# usbjtag.net
KiCad netlist of a schematic drawn in EAGLE
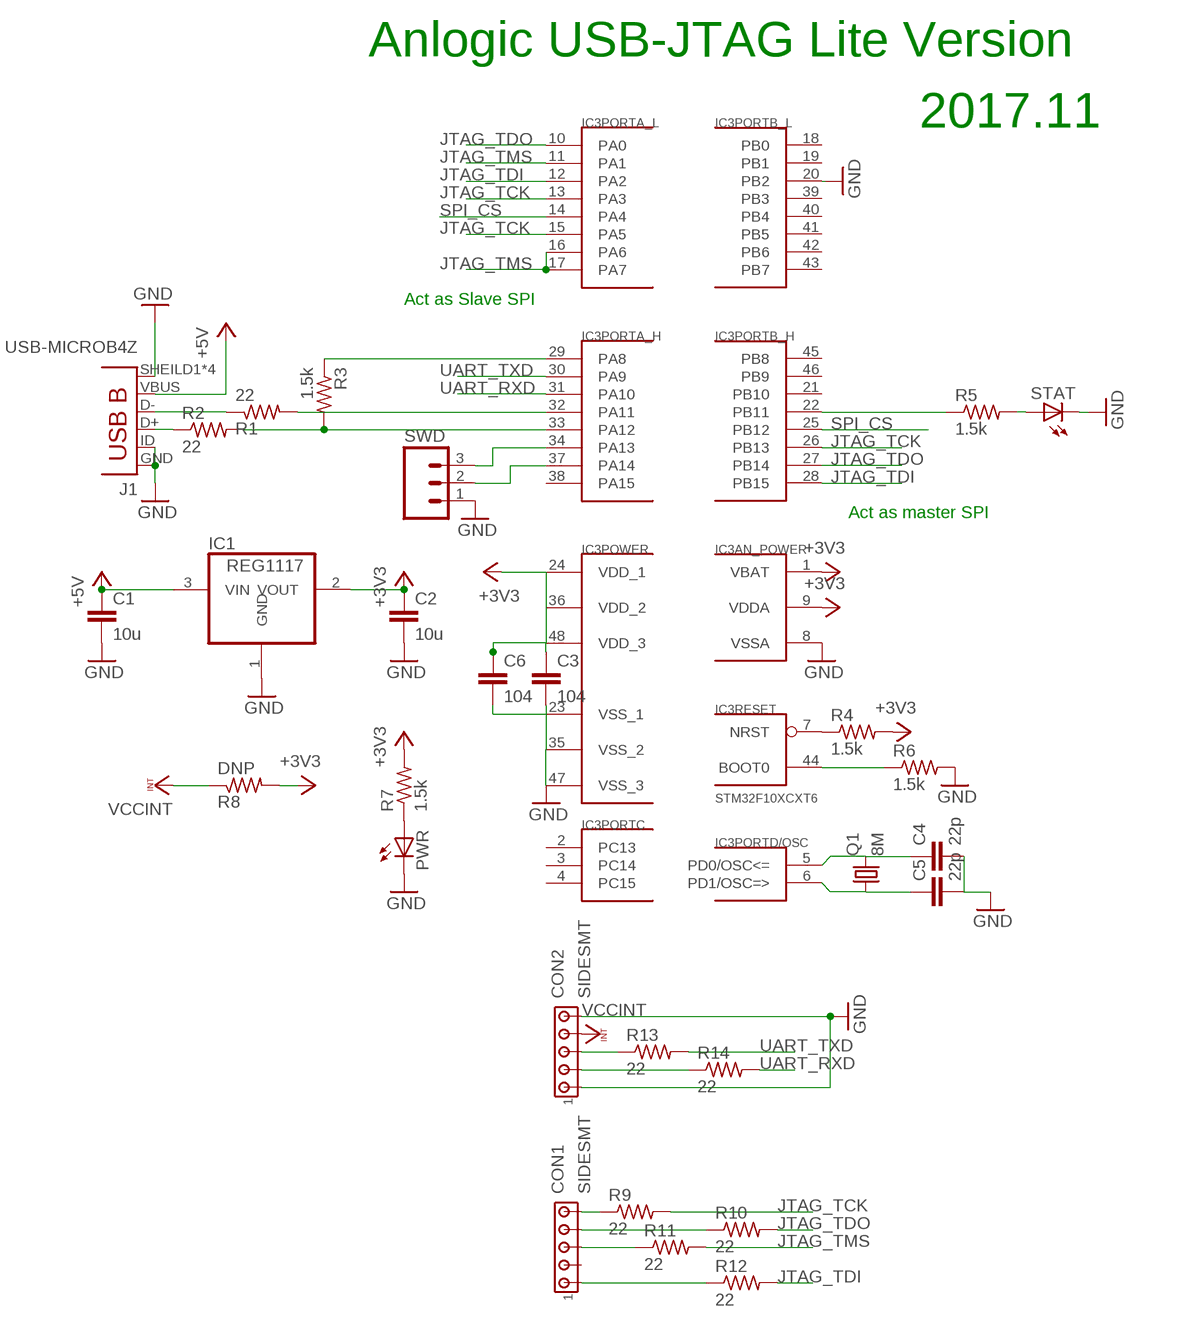
[diagram p0: schematic, sheet 1]

(export (version "E")
  (design (tool "Eeschema 10.0.6"))
  (components
    (comp (ref "C1")
      (value "10u")
      (footprint "eagle-import:C0805")
      (libsource (lib "eagle-import") (part "C-EUC0805"))
    )
    (comp (ref "C2")
      (value "10u")
      (footprint "eagle-import:C0805")
      (libsource (lib "eagle-import") (part "C-EUC0805"))
    )
    (comp (ref "C3")
      (value "104")
      (footprint "eagle-import:C0805")
      (libsource (lib "eagle-import") (part "C-EUC0805"))
    )
    (comp (ref "C4")
      (value "22p")
      (footprint "eagle-import:C0805")
      (libsource (lib "eagle-import") (part "C-EUC0805"))
    )
    (comp (ref "C5")
      (value "22p")
      (footprint "eagle-import:C0805")
      (libsource (lib "eagle-import") (part "C-EUC0805"))
    )
    (comp (ref "C6")
      (value "104")
      (footprint "eagle-import:C0805")
      (libsource (lib "eagle-import") (part "C-EUC0805"))
    )
    (comp (ref "CON1")
      (value "SIDESMT")
      (footprint "eagle-import:SIDESMT")
      (libsource (lib "eagle-import") (part "SIDESMT"))
    )
    (comp (ref "CON2")
      (value "SIDESMT")
      (footprint "eagle-import:SIDESMT")
      (libsource (lib "eagle-import") (part "SIDESMT"))
    )
    (comp (ref "IC1")
      (value "REG1117")
      (footprint "eagle-import:SOT223")
      (libsource (lib "eagle-import") (part "REG1117"))
    )
    (comp (ref "IC3")
      (value "STM32F10XCXT6")
      (footprint "eagle-import:TQFP48")
      (libsource (lib "eagle-import") (part "STM32F10XCXT6"))
    )
    (comp (ref "J1")
      (value "USB-MICROB4Z")
      (footprint "eagle-import:MICROUSB_4Z")
      (libsource (lib "eagle-import") (part "USB-MICROB4Z"))
    )
    (comp (ref "PWR")
      (value "LEDCHIP-LED0805")
      (footprint "eagle-import:CHIP-LED0805")
      (libsource (lib "eagle-import") (part "LEDCHIP-LED0805"))
    )
    (comp (ref "Q1")
      (value "8M")
      (footprint "eagle-import:HC49_S")
      (libsource (lib "eagle-import") (part "CRYSTALHC49S"))
    )
    (comp (ref "R1")
      (value "22")
      (footprint "eagle-import:M0805")
      (libsource (lib "eagle-import") (part "R-US_M0805"))
    )
    (comp (ref "R2")
      (value "22")
      (footprint "eagle-import:M0805")
      (libsource (lib "eagle-import") (part "R-US_M0805"))
    )
    (comp (ref "R3")
      (value "1.5k")
      (footprint "eagle-import:M0805")
      (libsource (lib "eagle-import") (part "R-US_M0805"))
    )
    (comp (ref "R4")
      (value "1.5k")
      (footprint "eagle-import:M0805")
      (libsource (lib "eagle-import") (part "R-US_M0805"))
    )
    (comp (ref "R5")
      (value "1.5k")
      (footprint "eagle-import:M0805")
      (libsource (lib "eagle-import") (part "R-US_M0805"))
    )
    (comp (ref "R6")
      (value "1.5k")
      (footprint "eagle-import:M0805")
      (libsource (lib "eagle-import") (part "R-US_M0805"))
    )
    (comp (ref "R7")
      (value "1.5k")
      (footprint "eagle-import:M0805")
      (libsource (lib "eagle-import") (part "R-US_M0805"))
    )
    (comp (ref "R8")
      (value "DNP")
      (footprint "eagle-import:M0805")
      (libsource (lib "eagle-import") (part "R-US_M0805"))
    )
    (comp (ref "R9")
      (value "22")
      (footprint "eagle-import:M0805")
      (libsource (lib "eagle-import") (part "R-US_M0805"))
    )
    (comp (ref "R10")
      (value "22")
      (footprint "eagle-import:M0805")
      (libsource (lib "eagle-import") (part "R-US_M0805"))
    )
    (comp (ref "R11")
      (value "22")
      (footprint "eagle-import:M0805")
      (libsource (lib "eagle-import") (part "R-US_M0805"))
    )
    (comp (ref "R12")
      (value "22")
      (footprint "eagle-import:M0805")
      (libsource (lib "eagle-import") (part "R-US_M0805"))
    )
    (comp (ref "R13")
      (value "22")
      (footprint "eagle-import:M0805")
      (libsource (lib "eagle-import") (part "R-US_M0805"))
    )
    (comp (ref "R14")
      (value "22")
      (footprint "eagle-import:M0805")
      (libsource (lib "eagle-import") (part "R-US_M0805"))
    )
    (comp (ref "STAT")
      (value "LEDCHIP-LED0805")
      (footprint "eagle-import:CHIP-LED0805")
      (libsource (lib "eagle-import") (part "LEDCHIP-LED0805"))
    )
    (comp (ref "SWD")
      (value "M03PTH")
      (footprint "eagle-import:1X03")
      (libsource (lib "eagle-import") (part "M03PTH"))
    )
  )
  (nets
    (net (code "1") (name "+3V3") (class "Default")
      (node (ref "C2") (pin "1") (pinfunction "1_1") (pintype "passive"))
      (node (ref "C3") (pin "1") (pinfunction "1_1") (pintype "passive"))
      (node (ref "C6") (pin "1") (pinfunction "1_1") (pintype "passive"))
      (node (ref "IC1") (pin "2") (pinfunction "VOUT_2") (pintype "output"))
      (node (ref "IC3") (pin "1") (pinfunction "VBAT_1") (pintype "power_in"))
      (node (ref "IC3") (pin "24") (pinfunction "VDD_1_24") (pintype "power_in"))
      (node (ref "IC3") (pin "36") (pinfunction "VDD_2_36") (pintype "power_in"))
      (node (ref "IC3") (pin "48") (pinfunction "VDD_3_48") (pintype "power_in"))
      (node (ref "IC3") (pin "9") (pinfunction "VDDA_9") (pintype "power_in"))
      (node (ref "R4") (pin "2") (pinfunction "2_2") (pintype "passive"))
      (node (ref "R7") (pin "2") (pinfunction "2_2") (pintype "passive"))
      (node (ref "R8") (pin "2") (pinfunction "2_2") (pintype "passive"))
    )
    (net (code "2") (name "+5V") (class "Default")
      (node (ref "C1") (pin "1") (pinfunction "1_1") (pintype "passive"))
      (node (ref "IC1") (pin "3") (pinfunction "VIN_3") (pintype "input"))
      (node (ref "J1") (pin "VBUS") (pinfunction "VBUS_VBUS") (pintype "bidirectional"))
    )
    (net (code "3") (name "/JTAG_TCK") (class "Default")
      (node (ref "IC3") (pin "13") (pinfunction "PA3_13") (pintype "bidirectional"))
      (node (ref "IC3") (pin "15") (pinfunction "PA5_15") (pintype "bidirectional"))
      (node (ref "IC3") (pin "26") (pinfunction "PB13_26") (pintype "bidirectional"))
      (node (ref "R9") (pin "2") (pinfunction "2_2") (pintype "passive"))
    )
    (net (code "4") (name "/JTAG_TDI") (class "Default")
      (node (ref "IC3") (pin "12") (pinfunction "PA2_12") (pintype "bidirectional"))
      (node (ref "IC3") (pin "28") (pinfunction "PB15_28") (pintype "bidirectional"))
      (node (ref "R12") (pin "2") (pinfunction "2_2") (pintype "passive"))
    )
    (net (code "5") (name "/JTAG_TDO") (class "Default")
      (node (ref "IC3") (pin "10") (pinfunction "PA0_10") (pintype "bidirectional"))
      (node (ref "IC3") (pin "27") (pinfunction "PB14_27") (pintype "bidirectional"))
      (node (ref "R10") (pin "2") (pinfunction "2_2") (pintype "passive"))
    )
    (net (code "6") (name "/JTAG_TMS") (class "Default")
      (node (ref "IC3") (pin "11") (pinfunction "PA1_11") (pintype "bidirectional"))
      (node (ref "IC3") (pin "16") (pinfunction "PA6_16") (pintype "bidirectional"))
      (node (ref "IC3") (pin "17") (pinfunction "PA7_17") (pintype "bidirectional"))
      (node (ref "R11") (pin "2") (pinfunction "2_2") (pintype "passive"))
    )
    (net (code "7") (name "/SPI_CS") (class "Default")
      (node (ref "IC3") (pin "14") (pinfunction "PA4_14") (pintype "bidirectional"))
      (node (ref "IC3") (pin "25") (pinfunction "PB12_25") (pintype "bidirectional"))
    )
    (net (code "8") (name "/UART_RXD") (class "Default")
      (node (ref "IC3") (pin "31") (pinfunction "PA10_31") (pintype "bidirectional"))
      (node (ref "R14") (pin "2") (pinfunction "2_2") (pintype "passive"))
    )
    (net (code "9") (name "/UART_TXD") (class "Default")
      (node (ref "IC3") (pin "30") (pinfunction "PA9_30") (pintype "bidirectional"))
      (node (ref "R13") (pin "2") (pinfunction "2_2") (pintype "passive"))
    )
    (net (code "10") (name "GND") (class "Default")
      (node (ref "C1") (pin "2") (pinfunction "2_2") (pintype "passive"))
      (node (ref "C2") (pin "2") (pinfunction "2_2") (pintype "passive"))
      (node (ref "C3") (pin "2") (pinfunction "2_2") (pintype "passive"))
      (node (ref "C4") (pin "2") (pinfunction "2_2") (pintype "passive"))
      (node (ref "C5") (pin "2") (pinfunction "2_2") (pintype "passive"))
      (node (ref "C6") (pin "2") (pinfunction "2_2") (pintype "passive"))
      (node (ref "CON2") (pin "1") (pinfunction "1_1") (pintype "passive"))
      (node (ref "CON2") (pin "5") (pinfunction "5_5") (pintype "passive"))
      (node (ref "IC1") (pin "1") (pinfunction "GND_1") (pintype "power_in"))
      (node (ref "IC3") (pin "20") (pinfunction "PB2_20") (pintype "bidirectional"))
      (node (ref "IC3") (pin "23") (pinfunction "VSS_1_23") (pintype "power_in"))
      (node (ref "IC3") (pin "35") (pinfunction "VSS_2_35") (pintype "power_in"))
      (node (ref "IC3") (pin "47") (pinfunction "VSS_3_47") (pintype "power_in"))
      (node (ref "IC3") (pin "8") (pinfunction "VSSA_8") (pintype "power_in"))
      (node (ref "J1") (pin "GND") (pinfunction "GND_GND") (pintype "bidirectional"))
      (node (ref "J1") (pin "ID") (pinfunction "USBID_ID") (pintype "bidirectional"))
      (node (ref "J1") (pin "SHEILD1") (pinfunction "SHIELD_SHEILD1") (pintype "bidirectional"))
      (node (ref "J1") (pin "SHEILD2") (pinfunction "SHIELD_SHEILD2") (pintype "bidirectional"))
      (node (ref "J1") (pin "SHEILD3") (pinfunction "SHIELD_SHEILD3") (pintype "bidirectional"))
      (node (ref "J1") (pin "SHEILD4") (pinfunction "SHIELD_SHEILD4") (pintype "bidirectional"))
      (node (ref "PWR") (pin "C") (pinfunction "C_C") (pintype "passive"))
      (node (ref "R6") (pin "2") (pinfunction "2_2") (pintype "passive"))
      (node (ref "STAT") (pin "C") (pinfunction "C_C") (pintype "passive"))
      (node (ref "SWD") (pin "1") (pinfunction "1_1") (pintype "passive"))
    )
    (net (code "11") (name "Net-(CON1-Pad1)") (class "Default")
      (node (ref "CON1") (pin "1") (pinfunction "1_1") (pintype "passive"))
      (node (ref "R12") (pin "1") (pinfunction "1_1") (pintype "passive"))
    )
    (net (code "12") (name "Net-(CON1-Pad3)") (class "Default")
      (node (ref "CON1") (pin "3") (pinfunction "3_3") (pintype "passive"))
      (node (ref "R11") (pin "1") (pinfunction "1_1") (pintype "passive"))
    )
    (net (code "13") (name "Net-(CON1-Pad4)") (class "Default")
      (node (ref "CON1") (pin "4") (pinfunction "4_4") (pintype "passive"))
      (node (ref "R10") (pin "1") (pinfunction "1_1") (pintype "passive"))
    )
    (net (code "14") (name "Net-(CON1-Pad5)") (class "Default")
      (node (ref "CON1") (pin "5") (pinfunction "5_5") (pintype "passive"))
      (node (ref "R9") (pin "1") (pinfunction "1_1") (pintype "passive"))
    )
    (net (code "15") (name "Net-(CON2-Pad2)") (class "Default")
      (node (ref "CON2") (pin "2") (pinfunction "2_2") (pintype "passive"))
      (node (ref "R14") (pin "1") (pinfunction "1_1") (pintype "passive"))
    )
    (net (code "16") (name "Net-(CON2-Pad3)") (class "Default")
      (node (ref "CON2") (pin "3") (pinfunction "3_3") (pintype "passive"))
      (node (ref "R13") (pin "1") (pinfunction "1_1") (pintype "passive"))
    )
    (net (code "17") (name "Net-(IC3B-PA8)") (class "Default")
      (node (ref "IC3") (pin "29") (pinfunction "PA8_29") (pintype "bidirectional"))
      (node (ref "R3") (pin "1") (pinfunction "1_1") (pintype "passive"))
    )
    (net (code "18") (name "Net-(IC3B-PA11)") (class "Default")
      (node (ref "IC3") (pin "32") (pinfunction "PA11_32") (pintype "bidirectional"))
      (node (ref "R1") (pin "2") (pinfunction "2_2") (pintype "passive"))
    )
    (net (code "19") (name "Net-(IC3B-PA12)") (class "Default")
      (node (ref "IC3") (pin "33") (pinfunction "PA12_33") (pintype "bidirectional"))
      (node (ref "R2") (pin "2") (pinfunction "2_2") (pintype "passive"))
      (node (ref "R3") (pin "2") (pinfunction "2_2") (pintype "passive"))
    )
    (net (code "20") (name "Net-(IC3B-PA13)") (class "Default")
      (node (ref "IC3") (pin "34") (pinfunction "PA13_34") (pintype "bidirectional"))
      (node (ref "SWD") (pin "3") (pinfunction "3_3") (pintype "passive"))
    )
    (net (code "21") (name "Net-(IC3B-PA14)") (class "Default")
      (node (ref "IC3") (pin "37") (pinfunction "PA14_37") (pintype "bidirectional"))
      (node (ref "SWD") (pin "2") (pinfunction "2_2") (pintype "passive"))
    )
    (net (code "22") (name "Net-(IC3D-PB11)") (class "Default")
      (node (ref "IC3") (pin "22") (pinfunction "PB11_22") (pintype "bidirectional"))
      (node (ref "R5") (pin "1") (pinfunction "1_1") (pintype "passive"))
    )
    (net (code "23") (name "Net-(IC3G-PD0{slash}OSC<=)") (class "Default")
      (node (ref "C4") (pin "1") (pinfunction "1_1") (pintype "passive"))
      (node (ref "IC3") (pin "5") (pinfunction "PD0/OSC<=_5") (pintype "bidirectional"))
      (node (ref "Q1") (pin "2") (pinfunction "2_2") (pintype "passive"))
    )
    (net (code "24") (name "Net-(IC3G-PD1{slash}OSC=>)") (class "Default")
      (node (ref "C5") (pin "1") (pinfunction "1_1") (pintype "passive"))
      (node (ref "IC3") (pin "6") (pinfunction "PD1/OSC=>_6") (pintype "bidirectional"))
      (node (ref "Q1") (pin "1") (pinfunction "1_1") (pintype "passive"))
    )
    (net (code "25") (name "Net-(IC3I-BOOT0)") (class "Default")
      (node (ref "IC3") (pin "44") (pinfunction "BOOT0_44") (pintype "input"))
      (node (ref "R6") (pin "1") (pinfunction "1_1") (pintype "passive"))
    )
    (net (code "26") (name "Net-(IC3I-NRST)") (class "Default")
      (node (ref "IC3") (pin "7") (pinfunction "NRST_7") (pintype "input"))
      (node (ref "R4") (pin "1") (pinfunction "1_1") (pintype "passive"))
    )
    (net (code "27") (name "Net-(J1-PadD+)") (class "Default")
      (node (ref "J1") (pin "D+") (pinfunction "D+_D+") (pintype "bidirectional"))
      (node (ref "R2") (pin "1") (pinfunction "1_1") (pintype "passive"))
    )
    (net (code "28") (name "Net-(J1-PadD-)") (class "Default")
      (node (ref "J1") (pin "D-") (pinfunction "D-_D-") (pintype "bidirectional"))
      (node (ref "R1") (pin "1") (pinfunction "1_1") (pintype "passive"))
    )
    (net (code "29") (name "Net-(PWR-PadA)") (class "Default")
      (node (ref "PWR") (pin "A") (pinfunction "A_A") (pintype "passive"))
      (node (ref "R7") (pin "1") (pinfunction "1_1") (pintype "passive"))
    )
    (net (code "30") (name "Net-(R5-Pad2)") (class "Default")
      (node (ref "R5") (pin "2") (pinfunction "2_2") (pintype "passive"))
      (node (ref "STAT") (pin "A") (pinfunction "A_A") (pintype "passive"))
    )
    (net (code "31") (name "VCCINT") (class "Default")
      (node (ref "CON2") (pin "4") (pinfunction "4_4") (pintype "passive"))
      (node (ref "R8") (pin "1") (pinfunction "1_1") (pintype "passive"))
    )
    (net (code "32") (name "unconnected-(CON1-Pad2)") (class "Default")
      (node (ref "CON1") (pin "2") (pinfunction "2_2") (pintype "passive"))
    )
    (net (code "33") (name "unconnected-(IC3B-PA15-Pad38)") (class "Default")
      (node (ref "IC3") (pin "38") (pinfunction "PA15_38") (pintype "bidirectional"))
    )
    (net (code "34") (name "unconnected-(IC3D-PB8-Pad45)") (class "Default")
      (node (ref "IC3") (pin "45") (pinfunction "PB8_45") (pintype "bidirectional"))
    )
    (net (code "35") (name "unconnected-(IC3D-PB9-Pad46)") (class "Default")
      (node (ref "IC3") (pin "46") (pinfunction "PB9_46") (pintype "bidirectional"))
    )
    (net (code "36") (name "unconnected-(IC3D-PB10-Pad21)") (class "Default")
      (node (ref "IC3") (pin "21") (pinfunction "PB10_21") (pintype "bidirectional"))
    )
    (net (code "37") (name "unconnected-(IC3E-PB0-Pad18)") (class "Default")
      (node (ref "IC3") (pin "18") (pinfunction "PB0_18") (pintype "bidirectional"))
    )
    (net (code "38") (name "unconnected-(IC3E-PB1-Pad19)") (class "Default")
      (node (ref "IC3") (pin "19") (pinfunction "PB1_19") (pintype "bidirectional"))
    )
    (net (code "39") (name "unconnected-(IC3E-PB3-Pad39)") (class "Default")
      (node (ref "IC3") (pin "39") (pinfunction "PB3_39") (pintype "bidirectional"))
    )
    (net (code "40") (name "unconnected-(IC3E-PB4-Pad40)") (class "Default")
      (node (ref "IC3") (pin "40") (pinfunction "PB4_40") (pintype "bidirectional"))
    )
    (net (code "41") (name "unconnected-(IC3E-PB5-Pad41)") (class "Default")
      (node (ref "IC3") (pin "41") (pinfunction "PB5_41") (pintype "bidirectional"))
    )
    (net (code "42") (name "unconnected-(IC3E-PB6-Pad42)") (class "Default")
      (node (ref "IC3") (pin "42") (pinfunction "PB6_42") (pintype "bidirectional"))
    )
    (net (code "43") (name "unconnected-(IC3E-PB7-Pad43)") (class "Default")
      (node (ref "IC3") (pin "43") (pinfunction "PB7_43") (pintype "bidirectional"))
    )
    (net (code "44") (name "unconnected-(IC3F-PC13-Pad2)") (class "Default")
      (node (ref "IC3") (pin "2") (pinfunction "PC13_2") (pintype "bidirectional"))
    )
    (net (code "45") (name "unconnected-(IC3F-PC14-Pad3)") (class "Default")
      (node (ref "IC3") (pin "3") (pinfunction "PC14_3") (pintype "bidirectional"))
    )
    (net (code "46") (name "unconnected-(IC3F-PC15-Pad4)") (class "Default")
      (node (ref "IC3") (pin "4") (pinfunction "PC15_4") (pintype "bidirectional"))
    )
  )
)
